# MCU.net
KiCad netlist of a schematic drawn in Altium Designer
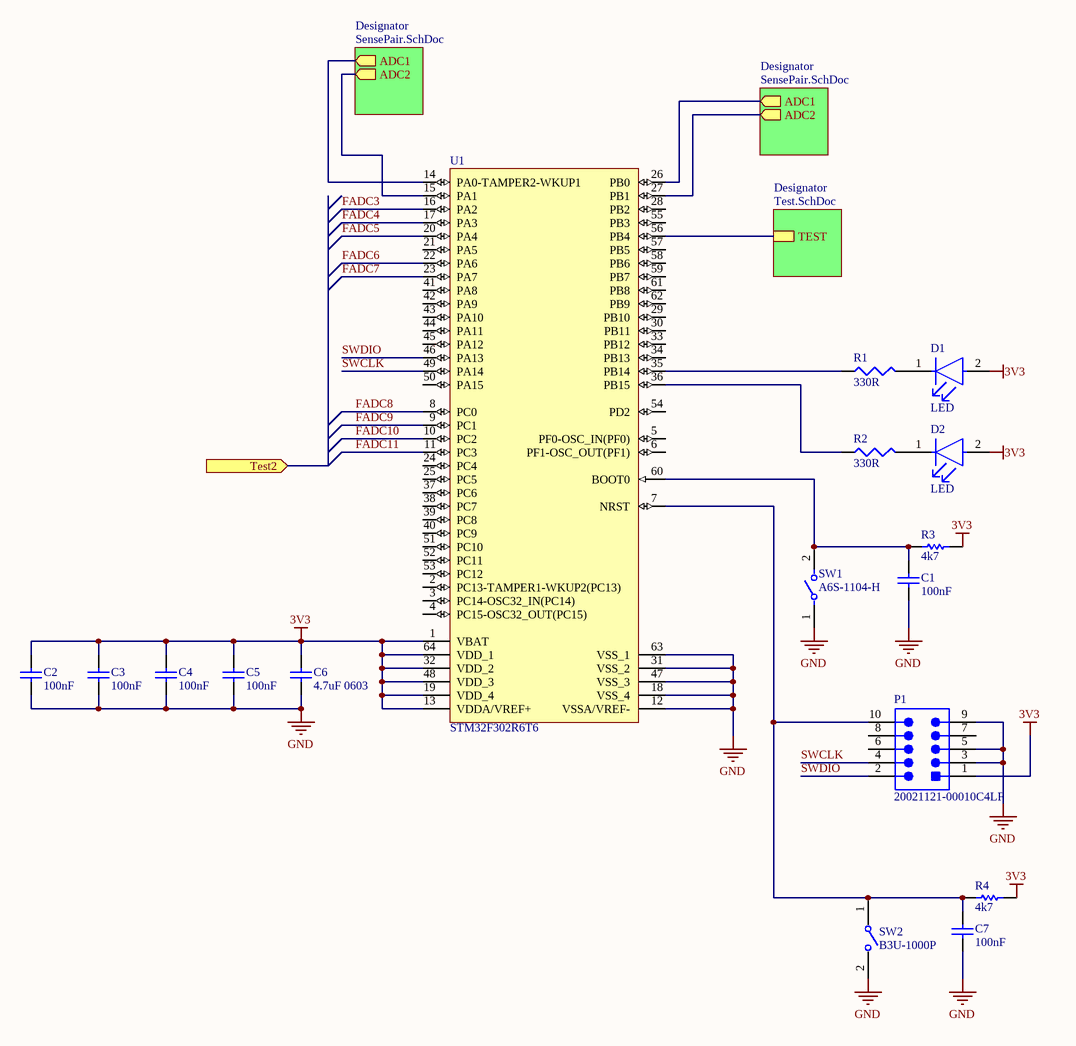
[diagram p0: MCU.SchDoc]

(export (version "E")
  (design (tool "Eeschema 10.0.6"))
  (components
    (comp (ref "C1")
      (value "100nF")
      (footprint "CAPC1608X90X35LL15T15")
      (description "Chip Capacitor, 100 nF, 25 V, -30 to 85 degC, 0603 (1608 Metric), RoHS, Tape and Reel")
      (fields (field (name "MANUFACTURER") "AVX"))
      (libsource (lib "Altium Content Vault") (part "CAP-NP-2"))
    )
    (comp (ref "C2")
      (value "100nF")
      (footprint "CAPC1608X90X35LL15T15")
      (description "Chip Capacitor, 100 nF, 25 V, -30 to 85 degC, 0603 (1608 Metric), RoHS, Tape and Reel")
      (fields (field (name "MANUFACTURER") "AVX"))
      (libsource (lib "Altium Content Vault") (part "CAP-NP-2"))
    )
    (comp (ref "C3")
      (value "100nF")
      (footprint "CAPC1608X90X35LL15T15")
      (description "Chip Capacitor, 100 nF, 25 V, -30 to 85 degC, 0603 (1608 Metric), RoHS, Tape and Reel")
      (fields (field (name "MANUFACTURER") "AVX"))
      (libsource (lib "Altium Content Vault") (part "CAP-NP-2"))
    )
    (comp (ref "C4")
      (value "100nF")
      (footprint "CAPC1608X90X35LL15T15")
      (description "Chip Capacitor, 100 nF, 25 V, -30 to 85 degC, 0603 (1608 Metric), RoHS, Tape and Reel")
      (fields (field (name "MANUFACTURER") "AVX"))
      (libsource (lib "Altium Content Vault") (part "CAP-NP-2"))
    )
    (comp (ref "C5")
      (value "100nF")
      (footprint "CAPC1608X90X35LL15T15")
      (description "Chip Capacitor, 100 nF, 25 V, -30 to 85 degC, 0603 (1608 Metric), RoHS, Tape and Reel")
      (fields (field (name "MANUFACTURER") "AVX"))
      (libsource (lib "Altium Content Vault") (part "CAP-NP-2"))
    )
    (comp (ref "C6")
      (value "4.7uF 0603")
      (footprint "CAPC1608X90X30LL10T20")
      (description "Chip Capacitor, 4.7 uF, +/- 10%, 6.3 V, -55 to 85 degC, 0603 (1608 Metric), RoHS, Tape and Reel")
      (fields (field (name "MANUFACTURER") "Samsung Electro-Mechanics"))
      (libsource (lib "Altium Content Vault") (part "CAP-NP-2"))
    )
    (comp (ref "C7")
      (value "100nF")
      (footprint "CAPC1608X90X35LL15T15")
      (description "Chip Capacitor, 100 nF, 25 V, -30 to 85 degC, 0603 (1608 Metric), RoHS, Tape and Reel")
      (fields (field (name "MANUFACTURER") "AVX"))
      (libsource (lib "Altium Content Vault") (part "CAP-NP-2"))
    )
    (comp (ref "D1")
      (value "LED")
      (footprint "FP-LTST-C191TBKT-MFG")
      (description "LED BLUE CLEAR CHIP SMD")
      (libsource (lib "Altium Content Vault") (part "8706943c75ba83719d021d2fdc84c58"))
    )
    (comp (ref "D2")
      (value "LED")
      (footprint "FP-LTST-C191TBKT-MFG")
      (description "LED BLUE CLEAR CHIP SMD")
      (libsource (lib "Altium Content Vault") (part "8706943c75ba83719d021d2fdc84c58"))
    )
    (comp (ref "P1")
      (value "20021121-00010C4LF")
      (footprint "HDR2X5_SMT")
      (description "Male Header, Pitch 1.27 mm, 2 x 5 Position, Height 4.55 mm, -40 to 85 degC, RoHS, Tape and Reel")
      (fields (field (name "MANUFACTURER") "FCI"))
      (libsource (lib "Altium Content Vault") (part "CN-2P-M-R10"))
    )
    (comp (ref "R1")
      (value "330R")
      (footprint "J1-0603")
      (description "Resistor")
      (fields (field (name "PUBLISHER") "Altium Limited"))
      (libsource (lib "Miscellaneous Devices") (part "Res3"))
    )
    (comp (ref "R2")
      (value "330R")
      (footprint "J1-0603")
      (description "Resistor")
      (fields (field (name "PUBLISHER") "Altium Limited"))
      (libsource (lib "Miscellaneous Devices") (part "Res3"))
    )
    (comp (ref "R3")
      (value "4k7")
      (footprint "RESC1608X55X25LL10T15")
      (description "Chip Resistor, 4.7 KOhm, +/- 1%, 0.1 W, -55 to 155 degC, 0603 (1608 Metric), RoHS, Tape and Reel")
      (fields (field (name "MANUFACTURER") "Yageo") (field (name "TOLERANCE") "1%"))
      (libsource (lib "Altium Content Vault") (part "RES-2"))
    )
    (comp (ref "R4")
      (value "4k7")
      (footprint "RESC1608X55X25LL10T15")
      (description "Chip Resistor, 4.7 KOhm, +/- 1%, 0.1 W, -55 to 155 degC, 0603 (1608 Metric), RoHS, Tape and Reel")
      (fields (field (name "MANUFACTURER") "Yageo") (field (name "TOLERANCE") "1%"))
      (libsource (lib "Altium Content Vault") (part "RES-2"))
    )
    (comp (ref "SW1")
      (value "A6S-1104-H")
      (footprint "FP-A6S-1104-H-MFG")
      (description "SWITCH SLIDE DIP SPST 25MA 24V")
      (fields
        (field (name "MANUFACTURER") "Omron Electronics Inc-EMC Div")
        (field (name "OCTOPART") "https://octopart.com/a6s-1104-h-omron-55410938")
      )
      (libsource (lib "Altium Content Vault") (part "bb27bde45df87f1f469753f287ef5ae"))
    )
    (comp (ref "SW2")
      (value "B3U-1000P")
      (footprint "FP-B3U-1000P-MFG")
      (description "SWITCH TACTILE SPST-NO 0.05A 12V")
      (libsource (lib "Altium Content Vault") (part "ae622034201233ca1abcedc05908f33"))
    )
    (comp (ref "U1")
      (value "STM32F302R6T6")
      (footprint "STM-LQFP64_L")
      (libsource (lib "Altium Content Vault") (part "MC-ARM-STM32F30X-LQFP64"))
    )
  )
  (nets
    (net (code "1") (name "/ADC1") (class "Default")
      (node (ref "U1") (pin "26") (pinfunction "PB0_26") (pintype "bidirectional"))
    )
    (net (code "2") (name "/ADC1_1") (class "Default")
      (node (ref "U1") (pin "14") (pinfunction "PA0-TAMPER2-WKUP1_14") (pintype "bidirectional"))
    )
    (net (code "3") (name "/ADC2") (class "Default")
      (node (ref "U1") (pin "27") (pinfunction "PB1_27") (pintype "bidirectional"))
    )
    (net (code "4") (name "/ADC2_1") (class "Default")
      (node (ref "U1") (pin "15") (pinfunction "PA1_15") (pintype "bidirectional"))
    )
    (net (code "5") (name "/FADC3") (class "Default")
      (node (ref "U1") (pin "16") (pinfunction "PA2_16") (pintype "bidirectional"))
    )
    (net (code "6") (name "/FADC4") (class "Default")
      (node (ref "U1") (pin "17") (pinfunction "PA3_17") (pintype "bidirectional"))
    )
    (net (code "7") (name "/FADC5") (class "Default")
      (node (ref "U1") (pin "20") (pinfunction "PA4_20") (pintype "bidirectional"))
    )
    (net (code "8") (name "/FADC6") (class "Default")
      (node (ref "U1") (pin "22") (pinfunction "PA6_22") (pintype "bidirectional"))
    )
    (net (code "9") (name "/FADC7") (class "Default")
      (node (ref "U1") (pin "23") (pinfunction "PA7_23") (pintype "bidirectional"))
    )
    (net (code "10") (name "/FADC8") (class "Default")
      (node (ref "U1") (pin "8") (pinfunction "PC0_8") (pintype "bidirectional"))
    )
    (net (code "11") (name "/FADC9") (class "Default")
      (node (ref "U1") (pin "9") (pinfunction "PC1_9") (pintype "bidirectional"))
    )
    (net (code "12") (name "/FADC10") (class "Default")
      (node (ref "U1") (pin "10") (pinfunction "PC2_10") (pintype "bidirectional"))
    )
    (net (code "13") (name "/FADC11") (class "Default")
      (node (ref "U1") (pin "11") (pinfunction "PC3_11") (pintype "bidirectional"))
    )
    (net (code "14") (name "/SWCLK") (class "Default")
      (node (ref "P1") (pin "4") (pinfunction "4_4") (pintype "passive"))
      (node (ref "U1") (pin "49") (pinfunction "PA14_49") (pintype "bidirectional"))
    )
    (net (code "15") (name "/SWDIO") (class "Default")
      (node (ref "P1") (pin "2") (pinfunction "2_2") (pintype "passive"))
      (node (ref "U1") (pin "46") (pinfunction "PA13_46") (pintype "bidirectional"))
    )
    (net (code "16") (name "/TEST") (class "Default")
      (node (ref "U1") (pin "56") (pinfunction "PB4_56") (pintype "bidirectional"))
    )
    (net (code "18") (name "3V3") (class "Default")
      (node (ref "C2") (pin "2") (pinfunction "2_2") (pintype "passive"))
      (node (ref "C3") (pin "2") (pinfunction "2_2") (pintype "passive"))
      (node (ref "C4") (pin "2") (pinfunction "2_2") (pintype "passive"))
      (node (ref "C5") (pin "2") (pinfunction "2_2") (pintype "passive"))
      (node (ref "C6") (pin "2") (pinfunction "2_2") (pintype "passive"))
      (node (ref "D1") (pin "2") (pinfunction "A_2") (pintype "passive"))
      (node (ref "D2") (pin "2") (pinfunction "A_2") (pintype "passive"))
      (node (ref "P1") (pin "1") (pinfunction "1_1") (pintype "passive"))
      (node (ref "R3") (pin "1") (pinfunction "1_1") (pintype "passive"))
      (node (ref "R4") (pin "1") (pinfunction "1_1") (pintype "passive"))
      (node (ref "U1") (pin "1") (pinfunction "VBAT_1") (pintype "power_in"))
      (node (ref "U1") (pin "13") (pinfunction "VDDA/VREF+_13") (pintype "power_in"))
      (node (ref "U1") (pin "19") (pinfunction "VDD_4_19") (pintype "power_in"))
      (node (ref "U1") (pin "32") (pinfunction "VDD_2_32") (pintype "power_in"))
      (node (ref "U1") (pin "48") (pinfunction "VDD_3_48") (pintype "power_in"))
      (node (ref "U1") (pin "64") (pinfunction "VDD_1_64") (pintype "power_in"))
    )
    (net (code "19") (name "GND") (class "Default")
      (node (ref "C1") (pin "1") (pinfunction "1_1") (pintype "passive"))
      (node (ref "C2") (pin "1") (pinfunction "1_1") (pintype "passive"))
      (node (ref "C3") (pin "1") (pinfunction "1_1") (pintype "passive"))
      (node (ref "C4") (pin "1") (pinfunction "1_1") (pintype "passive"))
      (node (ref "C5") (pin "1") (pinfunction "1_1") (pintype "passive"))
      (node (ref "C6") (pin "1") (pinfunction "1_1") (pintype "passive"))
      (node (ref "C7") (pin "1") (pinfunction "1_1") (pintype "passive"))
      (node (ref "P1") (pin "3") (pinfunction "3_3") (pintype "passive"))
      (node (ref "P1") (pin "5") (pinfunction "5_5") (pintype "passive"))
      (node (ref "P1") (pin "9") (pinfunction "9_9") (pintype "passive"))
      (node (ref "SW1") (pin "1") (pinfunction "1_1") (pintype "passive"))
      (node (ref "SW2") (pin "2") (pinfunction "2_2") (pintype "passive"))
      (node (ref "U1") (pin "12") (pinfunction "VSSA/VREF-_12") (pintype "power_in"))
      (node (ref "U1") (pin "18") (pinfunction "VSS_4_18") (pintype "power_in"))
      (node (ref "U1") (pin "31") (pinfunction "VSS_2_31") (pintype "power_in"))
      (node (ref "U1") (pin "47") (pinfunction "VSS_3_47") (pintype "power_in"))
      (node (ref "U1") (pin "63") (pinfunction "VSS_1_63") (pintype "power_in"))
    )
    (net (code "20") (name "Net-(D1-C)") (class "Default")
      (node (ref "D1") (pin "1") (pinfunction "C_1") (pintype "passive"))
      (node (ref "R1") (pin "2") (pinfunction "2_2") (pintype "passive"))
    )
    (net (code "21") (name "Net-(D2-C)") (class "Default")
      (node (ref "D2") (pin "1") (pinfunction "C_1") (pintype "passive"))
      (node (ref "R2") (pin "2") (pinfunction "2_2") (pintype "passive"))
    )
    (net (code "22") (name "Net-(U1-BOOT0)") (class "Default")
      (node (ref "C1") (pin "2") (pinfunction "2_2") (pintype "passive"))
      (node (ref "R3") (pin "2") (pinfunction "2_2") (pintype "passive"))
      (node (ref "SW1") (pin "2") (pinfunction "2_2") (pintype "passive"))
      (node (ref "U1") (pin "60") (pinfunction "BOOT0_60") (pintype "input"))
    )
    (net (code "23") (name "Net-(U1-NRST)") (class "Default")
      (node (ref "C7") (pin "2") (pinfunction "2_2") (pintype "passive"))
      (node (ref "P1") (pin "10") (pinfunction "10_10") (pintype "passive"))
      (node (ref "R4") (pin "2") (pinfunction "2_2") (pintype "passive"))
      (node (ref "SW2") (pin "1") (pinfunction "1_1") (pintype "passive"))
      (node (ref "U1") (pin "7") (pinfunction "NRST_7") (pintype "bidirectional"))
    )
    (net (code "24") (name "Net-(U1-PB14)") (class "Default")
      (node (ref "R1") (pin "1") (pinfunction "1_1") (pintype "passive"))
      (node (ref "U1") (pin "35") (pinfunction "PB14_35") (pintype "bidirectional"))
    )
    (net (code "25") (name "Net-(U1-PB15)") (class "Default")
      (node (ref "R2") (pin "1") (pinfunction "1_1") (pintype "passive"))
      (node (ref "U1") (pin "36") (pinfunction "PB15_36") (pintype "bidirectional"))
    )
    (net (code "26") (name "unconnected-(P1-Pad6)") (class "Default")
      (node (ref "P1") (pin "6") (pinfunction "6_6") (pintype "passive"))
    )
    (net (code "27") (name "unconnected-(P1-Pad7)") (class "Default")
      (node (ref "P1") (pin "7") (pinfunction "7_7") (pintype "passive"))
    )
    (net (code "28") (name "unconnected-(P1-Pad8)") (class "Default")
      (node (ref "P1") (pin "8") (pinfunction "8_8") (pintype "passive"))
    )
    (net (code "29") (name "unconnected-(U1-PA5-Pad21)") (class "Default")
      (node (ref "U1") (pin "21") (pinfunction "PA5_21") (pintype "bidirectional"))
    )
    (net (code "30") (name "unconnected-(U1-PA8-Pad41)") (class "Default")
      (node (ref "U1") (pin "41") (pinfunction "PA8_41") (pintype "bidirectional"))
    )
    (net (code "31") (name "unconnected-(U1-PA9-Pad42)") (class "Default")
      (node (ref "U1") (pin "42") (pinfunction "PA9_42") (pintype "bidirectional"))
    )
    (net (code "32") (name "unconnected-(U1-PA10-Pad43)") (class "Default")
      (node (ref "U1") (pin "43") (pinfunction "PA10_43") (pintype "bidirectional"))
    )
    (net (code "33") (name "unconnected-(U1-PA11-Pad44)") (class "Default")
      (node (ref "U1") (pin "44") (pinfunction "PA11_44") (pintype "bidirectional"))
    )
    (net (code "34") (name "unconnected-(U1-PA12-Pad45)") (class "Default")
      (node (ref "U1") (pin "45") (pinfunction "PA12_45") (pintype "bidirectional"))
    )
    (net (code "35") (name "unconnected-(U1-PA15-Pad50)") (class "Default")
      (node (ref "U1") (pin "50") (pinfunction "PA15_50") (pintype "bidirectional"))
    )
    (net (code "36") (name "unconnected-(U1-PB2-Pad28)") (class "Default")
      (node (ref "U1") (pin "28") (pinfunction "PB2_28") (pintype "bidirectional"))
    )
    (net (code "37") (name "unconnected-(U1-PB3-Pad55)") (class "Default")
      (node (ref "U1") (pin "55") (pinfunction "PB3_55") (pintype "bidirectional"))
    )
    (net (code "38") (name "unconnected-(U1-PB5-Pad57)") (class "Default")
      (node (ref "U1") (pin "57") (pinfunction "PB5_57") (pintype "bidirectional"))
    )
    (net (code "39") (name "unconnected-(U1-PB6-Pad58)") (class "Default")
      (node (ref "U1") (pin "58") (pinfunction "PB6_58") (pintype "bidirectional"))
    )
    (net (code "40") (name "unconnected-(U1-PB7-Pad59)") (class "Default")
      (node (ref "U1") (pin "59") (pinfunction "PB7_59") (pintype "bidirectional"))
    )
    (net (code "41") (name "unconnected-(U1-PB8-Pad61)") (class "Default")
      (node (ref "U1") (pin "61") (pinfunction "PB8_61") (pintype "bidirectional"))
    )
    (net (code "42") (name "unconnected-(U1-PB9-Pad62)") (class "Default")
      (node (ref "U1") (pin "62") (pinfunction "PB9_62") (pintype "bidirectional"))
    )
    (net (code "43") (name "unconnected-(U1-PB10-Pad29)") (class "Default")
      (node (ref "U1") (pin "29") (pinfunction "PB10_29") (pintype "bidirectional"))
    )
    (net (code "44") (name "unconnected-(U1-PB11-Pad30)") (class "Default")
      (node (ref "U1") (pin "30") (pinfunction "PB11_30") (pintype "bidirectional"))
    )
    (net (code "45") (name "unconnected-(U1-PB12-Pad33)") (class "Default")
      (node (ref "U1") (pin "33") (pinfunction "PB12_33") (pintype "bidirectional"))
    )
    (net (code "46") (name "unconnected-(U1-PB13-Pad34)") (class "Default")
      (node (ref "U1") (pin "34") (pinfunction "PB13_34") (pintype "bidirectional"))
    )
    (net (code "47") (name "unconnected-(U1-PC4-Pad24)") (class "Default")
      (node (ref "U1") (pin "24") (pinfunction "PC4_24") (pintype "bidirectional"))
    )
    (net (code "48") (name "unconnected-(U1-PC5-Pad25)") (class "Default")
      (node (ref "U1") (pin "25") (pinfunction "PC5_25") (pintype "bidirectional"))
    )
    (net (code "49") (name "unconnected-(U1-PC6-Pad37)") (class "Default")
      (node (ref "U1") (pin "37") (pinfunction "PC6_37") (pintype "bidirectional"))
    )
    (net (code "50") (name "unconnected-(U1-PC7-Pad38)") (class "Default")
      (node (ref "U1") (pin "38") (pinfunction "PC7_38") (pintype "bidirectional"))
    )
    (net (code "51") (name "unconnected-(U1-PC8-Pad39)") (class "Default")
      (node (ref "U1") (pin "39") (pinfunction "PC8_39") (pintype "bidirectional"))
    )
    (net (code "52") (name "unconnected-(U1-PC9-Pad40)") (class "Default")
      (node (ref "U1") (pin "40") (pinfunction "PC9_40") (pintype "bidirectional"))
    )
    (net (code "53") (name "unconnected-(U1-PC10-Pad51)") (class "Default")
      (node (ref "U1") (pin "51") (pinfunction "PC10_51") (pintype "bidirectional"))
    )
    (net (code "54") (name "unconnected-(U1-PC11-Pad52)") (class "Default")
      (node (ref "U1") (pin "52") (pinfunction "PC11_52") (pintype "bidirectional"))
    )
    (net (code "55") (name "unconnected-(U1-PC12-Pad53)") (class "Default")
      (node (ref "U1") (pin "53") (pinfunction "PC12_53") (pintype "bidirectional"))
    )
    (net (code "56") (name "unconnected-(U1-PC13-TAMPER1-WKUP2(PC13)-Pad2)") (class "Default")
      (node (ref "U1") (pin "2") (pinfunction "PC13-TAMPER1-WKUP2(PC13)_2") (pintype "bidirectional"))
    )
    (net (code "57") (name "unconnected-(U1-PC14-OSC32_IN(PC14)-Pad3)") (class "Default")
      (node (ref "U1") (pin "3") (pinfunction "PC14-OSC32_IN(PC14)_3") (pintype "bidirectional"))
    )
    (net (code "58") (name "unconnected-(U1-PC15-OSC32_OUT(PC15)-Pad4)") (class "Default")
      (node (ref "U1") (pin "4") (pinfunction "PC15-OSC32_OUT(PC15)_4") (pintype "bidirectional"))
    )
    (net (code "59") (name "unconnected-(U1-PD2-Pad54)") (class "Default")
      (node (ref "U1") (pin "54") (pinfunction "PD2_54") (pintype "bidirectional"))
    )
    (net (code "60") (name "unconnected-(U1-PF0-OSC_IN(PF0)-Pad5)") (class "Default")
      (node (ref "U1") (pin "5") (pinfunction "PF0-OSC_IN(PF0)_5") (pintype "bidirectional"))
    )
    (net (code "61") (name "unconnected-(U1-PF1-OSC_OUT(PF1)-Pad6)") (class "Default")
      (node (ref "U1") (pin "6") (pinfunction "PF1-OSC_OUT(PF1)_6") (pintype "bidirectional"))
    )
  )
)
